# Sheet1.net
KiCad netlist of a schematic drawn in Altium Designer
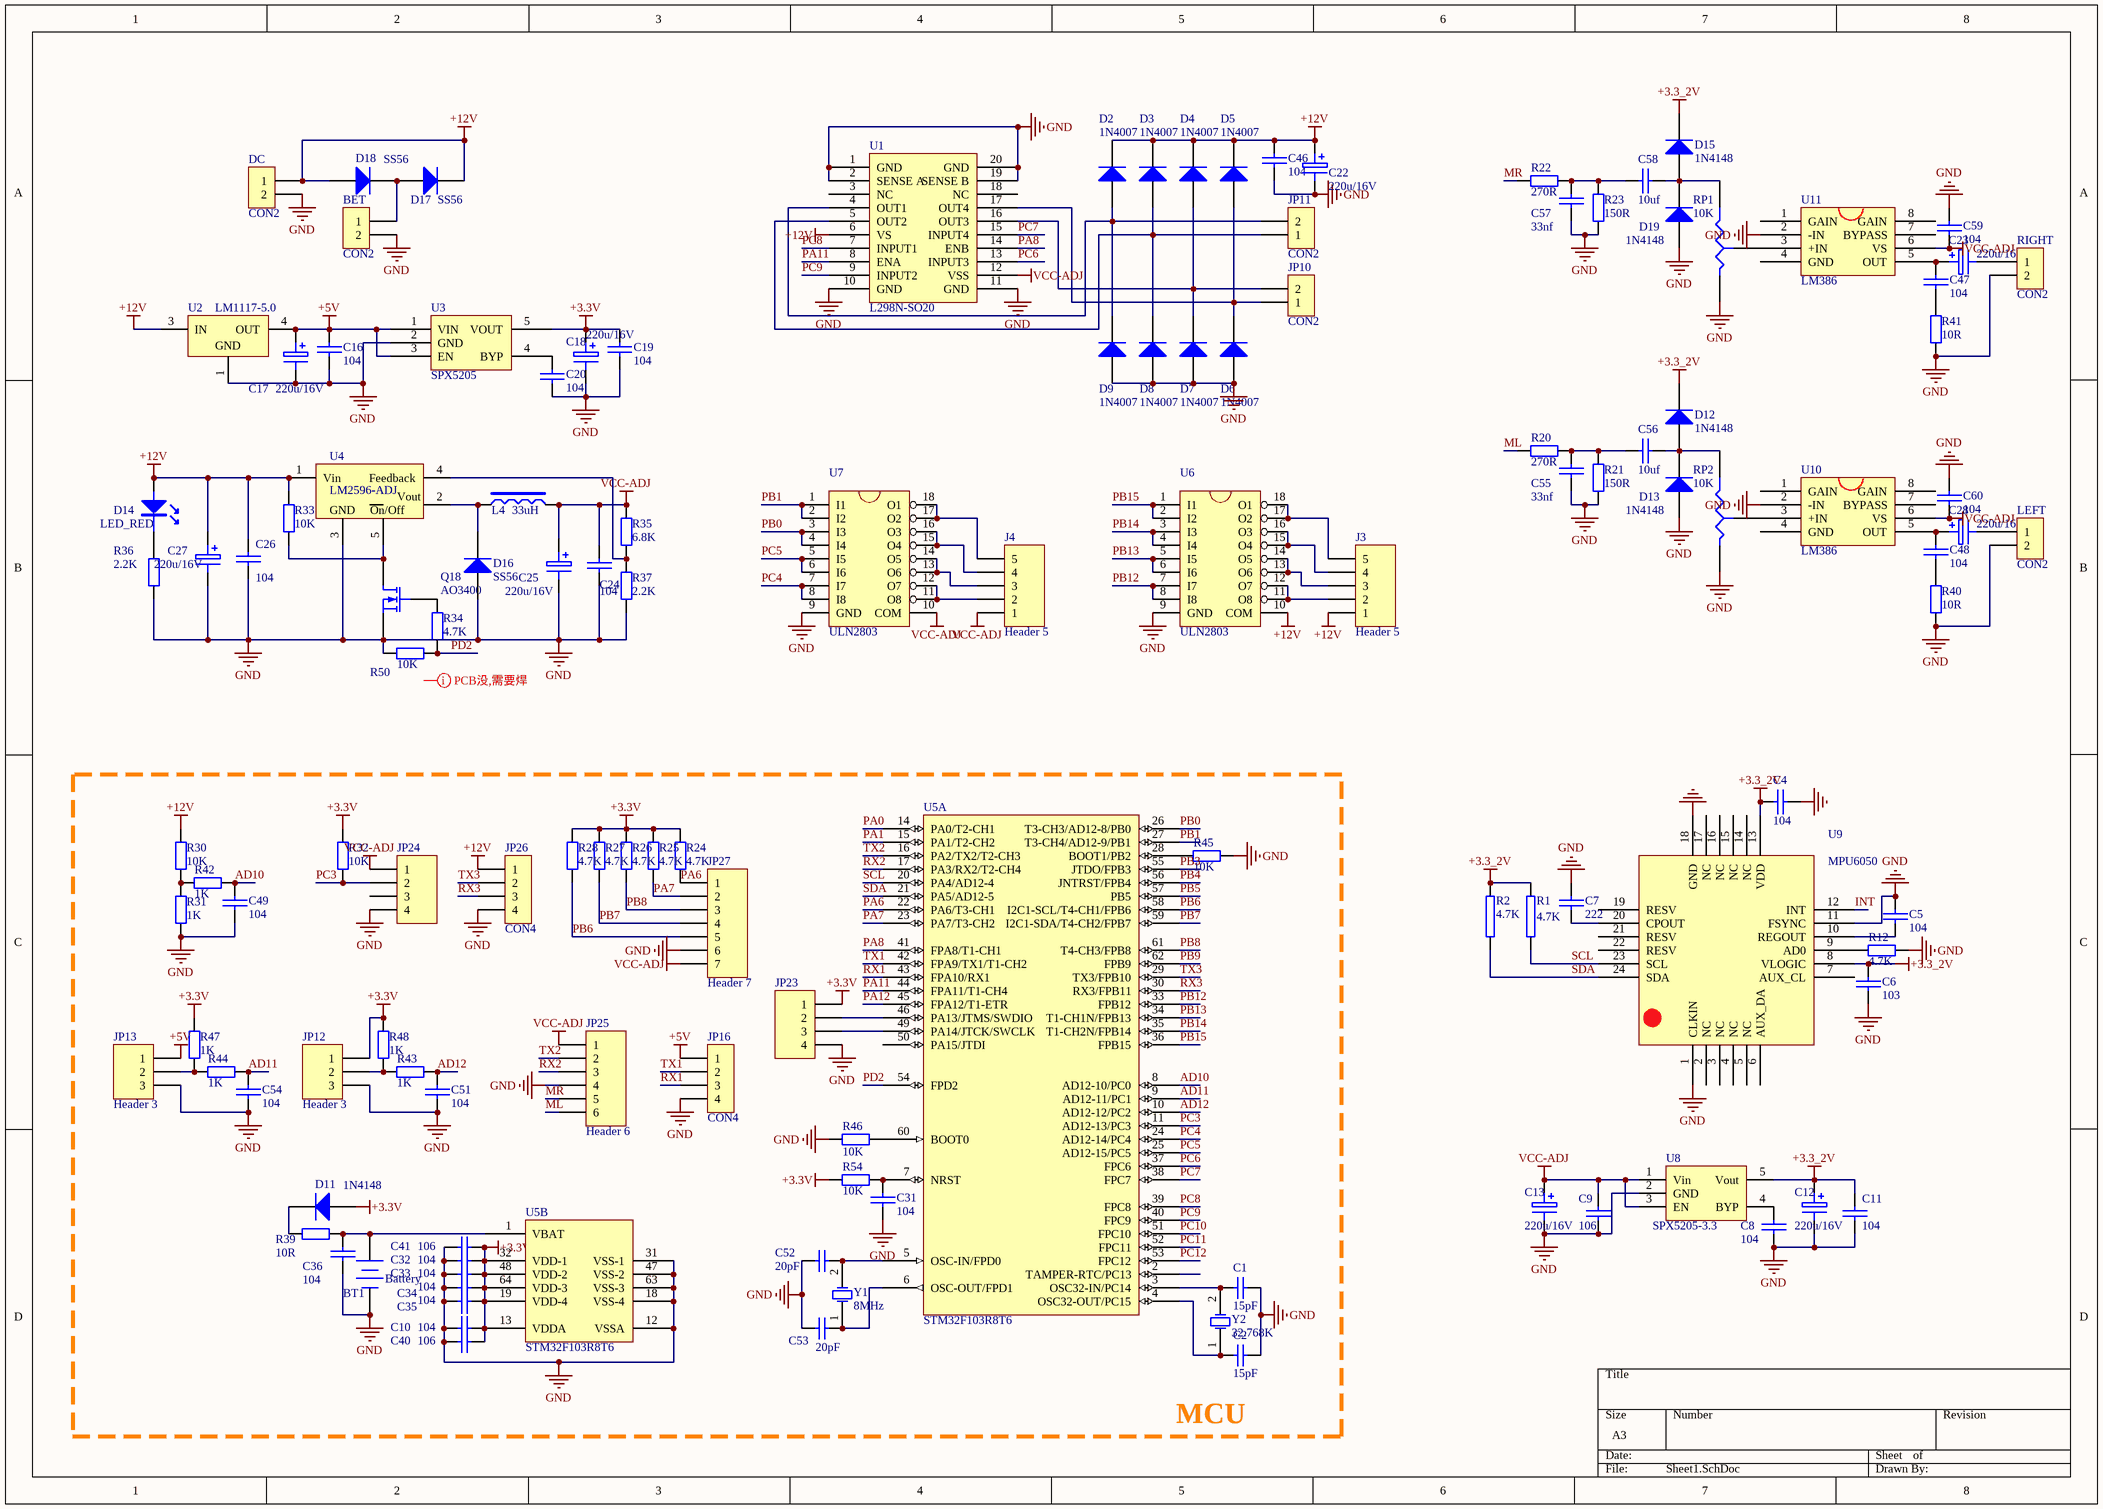
[diagram p0: Sheet1.SchDoc]

(export (version "E")
  (design (tool "Eeschema 10.0.6"))
  (components
    (comp (ref "BET")
      (value "CON2")
      (footprint "My Library:2PIN2.54")
      (description "Connector")
      (libsource (lib "*") (part "CON2"))
    )
    (comp (ref "BT1")
      (value "Battery")
      (footprint "BAT-2")
      (description "Multicell Battery")
      (fields (field (name "PUBLISHER") "Altium Limited"))
      (libsource (lib "Miscellaneous Devices") (part "Battery"))
    )
    (comp (ref "C1")
      (value "15pF")
      (footprint "0805")
      (description "Capacitor")
      (fields (field (name "PUBLISHER") "Altium Limited"))
      (libsource (lib "Miscellaneous Devices") (part "Cap"))
    )
    (comp (ref "C2")
      (value "15pF")
      (footprint "0805")
      (description "Capacitor")
      (fields (field (name "PUBLISHER") "Altium Limited"))
      (libsource (lib "Miscellaneous Devices") (part "Cap"))
    )
    (comp (ref "C4") (value "104") (footprint "0805") (libsource (lib "*") (part "CAP")))
    (comp (ref "C5") (value "104") (footprint "0805") (libsource (lib "*") (part "CAP_W")))
    (comp (ref "C6") (value "103") (footprint "0805") (libsource (lib "*") (part "CAP_W")))
    (comp (ref "C7") (value "222") (footprint "0805") (libsource (lib "*") (part "CAP_W")))
    (comp (ref "C8") (value "104") (footprint "0805") (libsource (lib "*") (part "CAP_W")))
    (comp (ref "C9") (value "106") (footprint "0805") (libsource (lib "*") (part "CAP_W")))
    (comp (ref "C10") (value "104") (footprint "0805") (libsource (lib "*") (part "CAP_W")))
    (comp (ref "C11") (value "104") (footprint "0805") (libsource (lib "*") (part "CAP_W")))
    (comp (ref "C12") (value "220u/16V") (footprint "C7542") (libsource (lib "*") (part "ELECTRO1_W")))
    (comp (ref "C13") (value "220u/16V") (footprint "C7542") (libsource (lib "*") (part "ELECTRO1_W")))
    (comp (ref "C16") (value "104") (footprint "0805") (libsource (lib "ddapwSch") (part "CAP_W")))
    (comp (ref "C17") (value "220u/16V") (footprint "C7542") (libsource (lib "*") (part "ELECTRO1_W")))
    (comp (ref "C18") (value "220u/16V") (footprint "C7542") (libsource (lib "*") (part "ELECTRO1_W")))
    (comp (ref "C19") (value "104") (footprint "0805") (libsource (lib "ddapwSch") (part "CAP_W")))
    (comp (ref "C20") (value "104") (footprint "0805") (libsource (lib "ddapwSch") (part "CAP_W")))
    (comp (ref "C22") (value "220u/16V") (footprint "C7542") (libsource (lib "*") (part "ELECTRO1_W")))
    (comp (ref "C23") (value "220u/16V") (footprint "C7542") (libsource (lib "*") (part "ELECTRO1_W")))
    (comp (ref "C24") (value "104") (footprint "0805") (libsource (lib "ddapwSch") (part "CAP_W")))
    (comp (ref "C25") (value "220u/16V") (footprint "C7542") (libsource (lib "*") (part "ELECTRO1_W")))
    (comp (ref "C26") (value "104") (footprint "0805") (libsource (lib "ddapwSch") (part "CAP_W")))
    (comp (ref "C27") (value "220u/16V") (footprint "C7542") (libsource (lib "*") (part "ELECTRO1_W")))
    (comp (ref "C28") (value "220u/16V") (footprint "C7542") (libsource (lib "*") (part "ELECTRO1_W")))
    (comp (ref "C31") (value "104") (footprint "0805") (libsource (lib "*") (part "CAP_W")))
    (comp (ref "C32") (value "104") (footprint "0805") (libsource (lib "*") (part "CAP_W")))
    (comp (ref "C33") (value "104") (footprint "0805") (libsource (lib "*") (part "CAP_W")))
    (comp (ref "C34") (value "104") (footprint "0805") (libsource (lib "*") (part "CAP_W")))
    (comp (ref "C35") (value "104") (footprint "0805") (libsource (lib "*") (part "CAP_W")))
    (comp (ref "C36") (value "104") (footprint "0805") (libsource (lib "*") (part "CAP_W")))
    (comp (ref "C40")
      (value "106")
      (footprint "0805")
      (description "Capacitor")
      (fields (field (name "PUBLISHER") "Altium Limited"))
      (libsource (lib "Miscellaneous Devices") (part "Cap"))
    )
    (comp (ref "C41")
      (value "106")
      (footprint "0805")
      (description "Capacitor")
      (fields (field (name "PUBLISHER") "Altium Limited"))
      (libsource (lib "Miscellaneous Devices") (part "Cap"))
    )
    (comp (ref "C46") (value "104") (footprint "0805") (libsource (lib "*") (part "CAP_W")))
    (comp (ref "C47") (value "104") (footprint "0805") (libsource (lib "*") (part "CAP_W")))
    (comp (ref "C48") (value "104") (footprint "0805") (libsource (lib "*") (part "CAP_W")))
    (comp (ref "C49") (value "104") (footprint "0805") (libsource (lib "*") (part "CAP_W")))
    (comp (ref "C51") (value "104") (footprint "0805") (libsource (lib "*") (part "CAP_W")))
    (comp (ref "C52")
      (value "20pF")
      (footprint "0805")
      (description "Capacitor")
      (fields (field (name "PUBLISHER") "Altium Limited"))
      (libsource (lib "Miscellaneous Devices") (part "Cap"))
    )
    (comp (ref "C53")
      (value "20pF")
      (footprint "My Library:0805")
      (description "Capacitor")
      (fields (field (name "PUBLISHER") "Altium Limited"))
      (libsource (lib "Miscellaneous Devices") (part "Cap"))
    )
    (comp (ref "C54") (value "104") (footprint "0805") (libsource (lib "*") (part "CAP_W")))
    (comp (ref "C55") (value "33nf") (footprint "0805") (libsource (lib "*") (part "CAP_W")))
    (comp (ref "C56") (value "10uf") (footprint "0805") (libsource (lib "") (part "CAP_W_1")))
    (comp (ref "C57") (value "33nf") (footprint "0805") (libsource (lib "*") (part "CAP_W")))
    (comp (ref "C58") (value "10uf") (footprint "0805") (libsource (lib "") (part "CAP_W_1")))
    (comp (ref "C59") (value "104") (footprint "0805") (libsource (lib "*") (part "CAP_W")))
    (comp (ref "C60") (value "104") (footprint "0805") (libsource (lib "*") (part "CAP_W")))
    (comp (ref "D2")
      (value "1N4007")
      (footprint "My Library:SMA")
      (description "Default Diode")
      (fields (field (name "PUBLISHER") "Altium Limited"))
      (libsource (lib "Miscellaneous Devices") (part "Diode"))
    )
    (comp (ref "D3")
      (value "1N4007")
      (footprint "My Library:SMA")
      (description "Default Diode")
      (fields (field (name "PUBLISHER") "Altium Limited"))
      (libsource (lib "Miscellaneous Devices") (part "Diode"))
    )
    (comp (ref "D4")
      (value "1N4007")
      (footprint "My Library:SMA")
      (description "Default Diode")
      (fields (field (name "PUBLISHER") "Altium Limited"))
      (libsource (lib "Miscellaneous Devices") (part "Diode"))
    )
    (comp (ref "D5")
      (value "1N4007")
      (footprint "My Library:SMA")
      (description "Default Diode")
      (fields (field (name "PUBLISHER") "Altium Limited"))
      (libsource (lib "Miscellaneous Devices") (part "Diode"))
    )
    (comp (ref "D6")
      (value "1N4007")
      (footprint "My Library:SMA")
      (description "Default Diode")
      (fields (field (name "PUBLISHER") "Altium Limited"))
      (libsource (lib "Miscellaneous Devices") (part "Diode"))
    )
    (comp (ref "D7")
      (value "1N4007")
      (footprint "My Library:SMA")
      (description "Default Diode")
      (fields (field (name "PUBLISHER") "Altium Limited"))
      (libsource (lib "Miscellaneous Devices") (part "Diode"))
    )
    (comp (ref "D8")
      (value "1N4007")
      (footprint "My Library:SMA")
      (description "Default Diode")
      (fields (field (name "PUBLISHER") "Altium Limited"))
      (libsource (lib "Miscellaneous Devices") (part "Diode"))
    )
    (comp (ref "D9")
      (value "1N4007")
      (footprint "My Library:SMA")
      (description "Default Diode")
      (fields (field (name "PUBLISHER") "Altium Limited"))
      (libsource (lib "Miscellaneous Devices") (part "Diode"))
    )
    (comp (ref "D11")
      (value "1N4148")
      (footprint "My Library:D1206")
      (description "Default Diode")
      (fields (field (name "PUBLISHER") "Altium Limited"))
      (libsource (lib "Miscellaneous Devices") (part "Diode"))
    )
    (comp (ref "D12")
      (value "1N4148")
      (footprint "My Library:D1206")
      (description "Default Diode")
      (fields (field (name "PUBLISHER") "Altium Limited"))
      (libsource (lib "Miscellaneous Devices") (part "Diode"))
    )
    (comp (ref "D13")
      (value "1N4148")
      (footprint "My Library:D1206")
      (description "Default Diode")
      (fields (field (name "PUBLISHER") "Altium Limited"))
      (libsource (lib "Miscellaneous Devices") (part "Diode"))
    )
    (comp (ref "D14")
      (value "LED_RED")
      (footprint "D0805")
      (libsource (lib "*") (part "Pro5E.tmp_UnNamed_101"))
    )
    (comp (ref "D15")
      (value "1N4148")
      (footprint "My Library:D1206")
      (description "Default Diode")
      (fields (field (name "PUBLISHER") "Altium Limited"))
      (libsource (lib "Miscellaneous Devices") (part "Diode"))
    )
    (comp (ref "D16")
      (value "SS56")
      (footprint "My Library:SMC")
      (description "Default Diode")
      (fields (field (name "PUBLISHER") "Altium Limited"))
      (libsource (lib "Miscellaneous Devices") (part "Diode"))
    )
    (comp (ref "D17")
      (value "SS56")
      (footprint "My Library:SMC")
      (description "Default Diode")
      (fields (field (name "PUBLISHER") "Altium Limited"))
      (libsource (lib "Miscellaneous Devices") (part "Diode"))
    )
    (comp (ref "D18")
      (value "SS56")
      (footprint "My Library:SMC")
      (description "Default Diode")
      (fields (field (name "PUBLISHER") "Altium Limited"))
      (libsource (lib "Miscellaneous Devices") (part "Diode"))
    )
    (comp (ref "D19")
      (value "1N4148")
      (footprint "My Library:D1206")
      (description "Default Diode")
      (fields (field (name "PUBLISHER") "Altium Limited"))
      (libsource (lib "Miscellaneous Devices") (part "Diode"))
    )
    (comp (ref "DC")
      (value "CON2")
      (footprint "My Library:2PIN2.54")
      (description "Connector")
      (libsource (lib "*") (part "CON2"))
    )
    (comp (ref "J3")
      (value "Header 5")
      (footprint "My Library:5PIN2.54")
      (description "Header, 5-Pin")
      (fields (field (name "PUBLISHER") "Altium Limited"))
      (libsource (lib "Miscellaneous Connectors") (part "Header 5"))
    )
    (comp (ref "J4")
      (value "Header 5")
      (footprint "My Library:5PIN2.54")
      (description "Header, 5-Pin")
      (fields (field (name "PUBLISHER") "Altium Limited"))
      (libsource (lib "Miscellaneous Connectors") (part "Header 5"))
    )
    (comp (ref "JP10")
      (value "CON2")
      (footprint "My Library:2PIN2.54")
      (description "Connector")
      (libsource (lib "") (part "CON2_1"))
    )
    (comp (ref "JP11")
      (value "CON2")
      (footprint "My Library:2PIN2.54")
      (description "Connector")
      (libsource (lib "") (part "CON2_1"))
    )
    (comp (ref "JP12")
      (value "Header 3")
      (footprint "My Library:3PIN2.54")
      (description "Header, 3-Pin")
      (fields (field (name "PUBLISHER") "Altium Limited"))
      (libsource (lib "Miscellaneous Connectors") (part "Header 3"))
    )
    (comp (ref "JP13")
      (value "Header 3")
      (footprint "My Library:3PIN2.54")
      (description "Header, 3-Pin")
      (fields (field (name "PUBLISHER") "Altium Limited"))
      (libsource (lib "Miscellaneous Connectors") (part "Header 3"))
    )
    (comp (ref "JP16")
      (value "CON4")
      (footprint "My Library:4PIN2.54")
      (description "Connector")
      (libsource (lib "Miscellaneous Devices") (part "CON4"))
    )
    (comp (ref "JP23")
      (value "Header 4")
      (footprint "My Library:4pin2.54-NEEDLE")
      (description "Header, 4-Pin")
      (fields (field (name "PUBLISHER") "Altium Limited"))
      (libsource (lib "Miscellaneous Connectors") (part "Header 4"))
    )
    (comp (ref "JP24")
      (value "Header 4")
      (footprint "My Library:4pin2.54-NEEDLE")
      (description "Header, 4-Pin")
      (fields (field (name "PUBLISHER") "Altium Limited"))
      (libsource (lib "") (part "Header 4_1"))
    )
    (comp (ref "JP25")
      (value "Header 6")
      (footprint "My Library:6PIN2.54")
      (description "Header, 6-Pin")
      (fields (field (name "PUBLISHER") "Altium Limited"))
      (libsource (lib "Miscellaneous Connectors") (part "Header 6"))
    )
    (comp (ref "JP26")
      (value "CON4")
      (footprint "My Library:4PIN2.54")
      (description "Connector")
      (libsource (lib "Miscellaneous Devices") (part "CON4"))
    )
    (comp (ref "JP27")
      (value "Header 7")
      (footprint "HDR1X7")
      (description "Header, 7-Pin")
      (fields (field (name "PUBLISHER") "Altium Limited"))
      (libsource (lib "Miscellaneous Connectors") (part "Header 7"))
    )
    (comp (ref "L4") (value "33uH") (footprint "SMD-12*12") (libsource (lib "*") (part "Pro4F.tmp_80uh_35")))
    (comp (ref "LEFT")
      (value "CON2")
      (footprint "My Library:2PIN2.54")
      (description "Connector")
      (libsource (lib "Miscellaneous Devices") (part "CON2"))
    )
    (comp (ref "Q18")
      (value "AO3400")
      (footprint "My Library:SOT-23-3")
      (description "N-Channel MOSFET")
      (fields (field (name "PUBLISHER") "Altium Limited"))
      (libsource (lib "Miscellaneous Devices") (part "MOSFET-N"))
    )
    (comp (ref "R1") (value "4.7K") (footprint "0805") (libsource (lib "*") (part "RES2")))
    (comp (ref "R2") (value "4.7K") (footprint "0805") (libsource (lib "*") (part "RES2")))
    (comp (ref "R12")
      (value "4.7K")
      (footprint "0805")
      (description "Resistor")
      (fields (field (name "PUBLISHER") "Altium Limited"))
      (libsource (lib "") (part "Res2_5"))
    )
    (comp (ref "R20")
      (value "270R")
      (footprint "My Library:0805")
      (description "Resistor")
      (fields (field (name "PUBLISHER") "Altium Limited"))
      (libsource (lib "") (part "Res2_1"))
    )
    (comp (ref "R21")
      (value "150R")
      (footprint "My Library:0805")
      (description "Resistor")
      (fields (field (name "PUBLISHER") "Altium Limited"))
      (libsource (lib "Miscellaneous Devices") (part "Res2"))
    )
    (comp (ref "R22")
      (value "270R")
      (footprint "My Library:0805")
      (description "Resistor")
      (fields (field (name "PUBLISHER") "Altium Limited"))
      (libsource (lib "") (part "Res2_7"))
    )
    (comp (ref "R23")
      (value "150R")
      (footprint "My Library:0805")
      (description "Resistor")
      (fields (field (name "PUBLISHER") "Altium Limited"))
      (libsource (lib "") (part "Res2_2"))
    )
    (comp (ref "R24")
      (value "4.7K")
      (footprint "My Library:0805")
      (description "Resistor")
      (fields (field (name "PUBLISHER") "Altium Limited"))
      (libsource (lib "") (part "Res2_2"))
    )
    (comp (ref "R25")
      (value "4.7K")
      (footprint "My Library:0805")
      (description "Resistor")
      (fields (field (name "PUBLISHER") "Altium Limited"))
      (libsource (lib "") (part "Res2_2"))
    )
    (comp (ref "R26")
      (value "4.7K")
      (footprint "My Library:0805")
      (description "Resistor")
      (fields (field (name "PUBLISHER") "Altium Limited"))
      (libsource (lib "") (part "Res2_2"))
    )
    (comp (ref "R27")
      (value "4.7K")
      (footprint "My Library:0805")
      (description "Resistor")
      (fields (field (name "PUBLISHER") "Altium Limited"))
      (libsource (lib "") (part "Res2_2"))
    )
    (comp (ref "R28")
      (value "4.7K")
      (footprint "My Library:0805")
      (description "Resistor")
      (fields (field (name "PUBLISHER") "Altium Limited"))
      (libsource (lib "") (part "Res2_2"))
    )
    (comp (ref "R30")
      (value "10K")
      (footprint "My Library:0805")
      (description "Resistor")
      (fields (field (name "PUBLISHER") "Altium Limited"))
      (libsource (lib "Miscellaneous Devices") (part "Res2"))
    )
    (comp (ref "R31")
      (value "1K")
      (footprint "My Library:0805")
      (description "Resistor")
      (fields (field (name "PUBLISHER") "Altium Limited"))
      (libsource (lib "Miscellaneous Devices") (part "Res2"))
    )
    (comp (ref "R32")
      (value "10K")
      (footprint "My Library:0805")
      (description "Resistor")
      (fields (field (name "PUBLISHER") "Altium Limited"))
      (libsource (lib "") (part "Res2_1"))
    )
    (comp (ref "R33")
      (value "10K")
      (footprint "0805")
      (description "Resistor")
      (fields (field (name "PUBLISHER") "Altium Limited"))
      (libsource (lib "") (part "Res2_3"))
    )
    (comp (ref "R34")
      (value "4.7K")
      (footprint "0805")
      (description "Resistor")
      (fields (field (name "PUBLISHER") "Altium Limited"))
      (libsource (lib "") (part "Res2_3"))
    )
    (comp (ref "R35")
      (value "6.8K")
      (footprint "0805")
      (description "Resistor")
      (fields (field (name "PUBLISHER") "Altium Limited"))
      (libsource (lib "") (part "Res2_6"))
    )
    (comp (ref "R36")
      (value "2.2K")
      (footprint "0805")
      (description "Resistor")
      (fields (field (name "PUBLISHER") "Altium Limited"))
      (libsource (lib "") (part "Res2_6"))
    )
    (comp (ref "R37")
      (value "2.2K")
      (footprint "0805")
      (description "Resistor")
      (fields (field (name "PUBLISHER") "Altium Limited"))
      (libsource (lib "") (part "Res2_6"))
    )
    (comp (ref "R39")
      (value "10R")
      (footprint "My Library:0805")
      (description "Resistor")
      (fields (field (name "PUBLISHER") "Altium Limited"))
      (libsource (lib "") (part "Res2_7"))
    )
    (comp (ref "R40")
      (value "10R")
      (footprint "My Library:0805")
      (description "Resistor")
      (fields (field (name "PUBLISHER") "Altium Limited"))
      (libsource (lib "") (part "Res2_2"))
    )
    (comp (ref "R41")
      (value "10R")
      (footprint "My Library:0805")
      (description "Resistor")
      (fields (field (name "PUBLISHER") "Altium Limited"))
      (libsource (lib "") (part "Res2_2"))
    )
    (comp (ref "R42")
      (value "1K")
      (footprint "My Library:0805")
      (description "Resistor")
      (fields (field (name "PUBLISHER") "Altium Limited"))
      (libsource (lib "") (part "Res2_1"))
    )
    (comp (ref "R43")
      (value "1K")
      (footprint "My Library:0805")
      (description "Resistor")
      (fields (field (name "PUBLISHER") "Altium Limited"))
      (libsource (lib "") (part "Res2_1"))
    )
    (comp (ref "R44")
      (value "1K")
      (footprint "My Library:0805")
      (description "Resistor")
      (fields (field (name "PUBLISHER") "Altium Limited"))
      (libsource (lib "") (part "Res2_1"))
    )
    (comp (ref "R45")
      (value "10K")
      (footprint "0805")
      (description "Resistor")
      (fields (field (name "PUBLISHER") "Altium Limited"))
      (libsource (lib "") (part "Res2_4"))
    )
    (comp (ref "R46")
      (value "10K")
      (footprint "0805")
      (description "Resistor")
      (fields (field (name "PUBLISHER") "Altium Limited"))
      (libsource (lib "") (part "Res2_4"))
    )
    (comp (ref "R47")
      (value "1K")
      (footprint "My Library:0805")
      (description "Resistor")
      (fields (field (name "PUBLISHER") "Altium Limited"))
      (libsource (lib "Miscellaneous Devices") (part "Res2"))
    )
    (comp (ref "R48")
      (value "1K")
      (footprint "My Library:0805")
      (description "Resistor")
      (fields (field (name "PUBLISHER") "Altium Limited"))
      (libsource (lib "Miscellaneous Devices") (part "Res2"))
    )
    (comp (ref "R50")
      (value "10K")
      (footprint "0805")
      (description "Resistor")
      (fields (field (name "PUBLISHER") "Altium Limited"))
      (libsource (lib "") (part "Res2_5"))
    )
    (comp (ref "R54")
      (value "10K")
      (footprint "My Library:0805")
      (description "Resistor")
      (fields (field (name "PUBLISHER") "Altium Limited"))
      (libsource (lib "Miscellaneous Devices") (part "Res2"))
    )
    (comp (ref "RIGHT")
      (value "CON2")
      (footprint "My Library:2PIN2.54")
      (description "Connector")
      (libsource (lib "Miscellaneous Devices") (part "CON2"))
    )
    (comp (ref "RP1")
      (value "10K")
      (footprint "My Library:RP")
      (description "Tapped Resistor")
      (fields (field (name "PUBLISHER") "Altium Limited"))
      (libsource (lib "Miscellaneous Devices") (part "Res Tap"))
    )
    (comp (ref "RP2")
      (value "10K")
      (footprint "My Library:RP")
      (description "Tapped Resistor")
      (fields (field (name "PUBLISHER") "Altium Limited"))
      (libsource (lib "Miscellaneous Devices") (part "Res Tap"))
    )
    (comp (ref "U1")
      (value "L298N-SO20")
      (footprint "PowerSO20")
      (libsource (lib "My Library") (part "L298N"))
    )
    (comp (ref "U2")
      (value "LM1117-5.0")
      (footprint "SOT-223")
      (description "800mA Low-Dropout Linear Regulator, 3-pin TO-252")
      (fields
        (field (name "PARTNUMBER") "LM1117IDT-3.3")
        (field (name "MANUFACTURER") "National Semiconductor")
        (field (name "PUBLISHER") "Altium Limited")
      )
      (libsource (lib "NSC LDO") (part "LM1117IDT-3.3"))
    )
    (comp (ref "U3")
      (value "SPX5205")
      (footprint "My Library:SOT-23-5")
      (description "VOLTAGE REGULATOR IC")
      (libsource (lib "DDD") (part "SPX5205"))
    )
    (comp (ref "U4") (value "LM2596-ADJ") (footprint "TO-263-5") (libsource (lib "*") (part "LM2575-5")))
    (comp (ref "U5")
      (value "STM32F103R8T6")
      (footprint "My Library:LTQFP64")
      (description "STM32 ARM-based 32-bit MCU with 64 Kbytes Flash, 64-pin LQFP, Industrial Temperature")
      (fields (field (name "PUBLISHER") "*"))
      (libsource (lib "STM32 SCH") (part "STM32F103R8T6"))
    )
    (comp (ref "U6")
      (value "ULN2803")
      (footprint "SOIC-18")
      (description "SOIC")
      (libsource (lib "IC集成芯片") (part "ULN2803"))
    )
    (comp (ref "U7")
      (value "ULN2803")
      (footprint "SOIC-18")
      (description "SOIC")
      (libsource (lib "IC集成芯片") (part "ULN2803"))
    )
    (comp (ref "U8")
      (value "SPX5205-3.3")
      (footprint "SOT-23-5")
      (libsource (lib "CMOSChip") (part "SPX5205"))
    )
    (comp (ref "U9")
      (value "MPU6050")
      (footprint "My Library:QFN4*4*0.9_24PIN")
      (libsource (lib "My Library") (part "MPU6050"))
    )
    (comp (ref "U10") (value "LM386") (footprint "SOP-8") (libsource (lib "My Library") (part "LM386")))
    (comp (ref "U11") (value "LM386") (footprint "SOP-8") (libsource (lib "My Library") (part "LM386")))
    (comp (ref "Y1")
      (value "8MHz")
      (footprint "My Library:SMD-5032")
      (description "Crystal Oscillator")
      (fields (field (name "PUBLISHER") "Altium Limited"))
      (libsource (lib "Miscellaneous Devices") (part "XTAL"))
    )
    (comp (ref "Y2")
      (value "32.768K")
      (footprint "My Library:SMD-5032")
      (description "Crystal Oscillator")
      (fields (field (name "PUBLISHER") "Altium Limited"))
      (libsource (lib "Miscellaneous Devices") (part "XTAL"))
    )
  )
  (nets
    (net (code "1") (name "+3.3V") (class "Default")
      (node (ref "C10") (pin "1") (pinfunction "1_1") (pintype "passive"))
      (node (ref "C18") (pin "1") (pinfunction "1_1") (pintype "passive"))
      (node (ref "C19") (pin "1") (pinfunction "1_1") (pintype "passive"))
      (node (ref "C32") (pin "2") (pinfunction "2_2") (pintype "passive"))
      (node (ref "C33") (pin "1") (pinfunction "1_1") (pintype "passive"))
      (node (ref "C34") (pin "2") (pinfunction "2_2") (pintype "passive"))
      (node (ref "C35") (pin "2") (pinfunction "2_2") (pintype "passive"))
      (node (ref "C40") (pin "2") (pinfunction "2_2") (pintype "passive"))
      (node (ref "C41") (pin "2") (pinfunction "2_2") (pintype "passive"))
      (node (ref "D11") (pin "1") (pinfunction "A_1") (pintype "passive"))
      (node (ref "JP12") (pin "1") (pinfunction "1_1") (pintype "passive"))
      (node (ref "JP23") (pin "1") (pinfunction "1_1") (pintype "passive"))
      (node (ref "R24") (pin "2") (pinfunction "2_2") (pintype "passive"))
      (node (ref "R25") (pin "2") (pinfunction "2_2") (pintype "passive"))
      (node (ref "R26") (pin "2") (pinfunction "2_2") (pintype "passive"))
      (node (ref "R27") (pin "2") (pinfunction "2_2") (pintype "passive"))
      (node (ref "R28") (pin "2") (pinfunction "2_2") (pintype "passive"))
      (node (ref "R32") (pin "1") (pinfunction "1_1") (pintype "passive"))
      (node (ref "R47") (pin "1") (pinfunction "1_1") (pintype "passive"))
      (node (ref "R48") (pin "1") (pinfunction "1_1") (pintype "passive"))
      (node (ref "R54") (pin "2") (pinfunction "2_2") (pintype "passive"))
      (node (ref "U3") (pin "5") (pinfunction "VOUT_5") (pintype "passive"))
      (node (ref "U5") (pin "13") (pinfunction "VDDA_13") (pintype "power_in"))
      (node (ref "U5") (pin "19") (pinfunction "VDD-4_19") (pintype "power_in"))
      (node (ref "U5") (pin "32") (pinfunction "VDD-1_32") (pintype "power_in"))
      (node (ref "U5") (pin "48") (pinfunction "VDD-2_48") (pintype "power_in"))
      (node (ref "U5") (pin "64") (pinfunction "VDD-3_64") (pintype "power_in"))
    )
    (net (code "2") (name "+3.3_2V") (class "Default")
      (node (ref "C11") (pin "2") (pinfunction "2_2") (pintype "passive"))
      (node (ref "C12") (pin "1") (pinfunction "1_1") (pintype "passive"))
      (node (ref "C4") (pin "1") (pintype "passive"))
      (node (ref "C6") (pin "1") (pinfunction "1_1") (pintype "passive"))
      (node (ref "D12") (pin "2") (pinfunction "K_2") (pintype "passive"))
      (node (ref "D15") (pin "2") (pinfunction "K_2") (pintype "passive"))
      (node (ref "R1") (pin "1") (pintype "passive"))
      (node (ref "R2") (pin "1") (pintype "passive"))
      (node (ref "U8") (pin "5") (pinfunction "Vout_5") (pintype "passive"))
      (node (ref "U9") (pin "13") (pinfunction "VDD_13") (pintype "passive"))
      (node (ref "U9") (pin "8") (pinfunction "VLOGIC_8") (pintype "passive"))
    )
    (net (code "3") (name "+5V") (class "Default")
      (node (ref "C16") (pin "1") (pinfunction "1_1") (pintype "passive"))
      (node (ref "C17") (pin "1") (pinfunction "1_1") (pintype "passive"))
      (node (ref "JP13") (pin "1") (pinfunction "1_1") (pintype "passive"))
      (node (ref "JP16") (pin "1") (pinfunction "1_1") (pintype "passive"))
      (node (ref "U2") (pin "4") (pinfunction "OUT_4") (pintype "power_in"))
      (node (ref "U3") (pin "1") (pinfunction "VIN_1") (pintype "passive"))
      (node (ref "U3") (pin "3") (pinfunction "EN_3") (pintype "passive"))
    )
    (net (code "4") (name "+12V") (class "Default")
      (node (ref "C22") (pin "1") (pinfunction "1_1") (pintype "passive"))
      (node (ref "C26") (pin "1") (pinfunction "1_1") (pintype "passive"))
      (node (ref "C27") (pin "1") (pinfunction "1_1") (pintype "passive"))
      (node (ref "C46") (pin "2") (pinfunction "2_2") (pintype "passive"))
      (node (ref "D14") (pin "A") (pintype "passive"))
      (node (ref "D17") (pin "2") (pinfunction "K_2") (pintype "passive"))
      (node (ref "D18") (pin "1") (pinfunction "A_1") (pintype "passive"))
      (node (ref "D2") (pin "2") (pinfunction "K_2") (pintype "passive"))
      (node (ref "D3") (pin "2") (pinfunction "K_2") (pintype "passive"))
      (node (ref "D4") (pin "2") (pinfunction "K_2") (pintype "passive"))
      (node (ref "D5") (pin "2") (pinfunction "K_2") (pintype "passive"))
      (node (ref "DC") (pin "1") (pinfunction "1_1") (pintype "passive"))
      (node (ref "J3") (pin "1") (pinfunction "1_1") (pintype "passive"))
      (node (ref "JP26") (pin "1") (pinfunction "1_1") (pintype "passive"))
      (node (ref "R30") (pin "1") (pinfunction "1_1") (pintype "passive"))
      (node (ref "R33") (pin "1") (pinfunction "1_1") (pintype "passive"))
      (node (ref "U1") (pin "6") (pinfunction "VS_6") (pintype "passive"))
      (node (ref "U2") (pin "3") (pinfunction "IN_3") (pintype "power_in"))
      (node (ref "U4") (pin "1") (pinfunction "Vin_1") (pintype "passive"))
      (node (ref "U6") (pin "10") (pinfunction "COM_10") (pintype "power_in"))
    )
    (net (code "5") (name "/AD10") (class "Default")
      (node (ref "C49") (pin "1") (pinfunction "1_1") (pintype "passive"))
      (node (ref "R42") (pin "1") (pinfunction "1_1") (pintype "passive"))
      (node (ref "U5") (pin "8") (pinfunction "AD12-10/PC0_8") (pintype "bidirectional"))
    )
    (net (code "6") (name "/AD11") (class "Default")
      (node (ref "C54") (pin "1") (pinfunction "1_1") (pintype "passive"))
      (node (ref "R44") (pin "1") (pinfunction "1_1") (pintype "passive"))
      (node (ref "U5") (pin "9") (pinfunction "AD12-11/PC1_9") (pintype "bidirectional"))
    )
    (net (code "7") (name "/AD12") (class "Default")
      (node (ref "C51") (pin "1") (pinfunction "1_1") (pintype "passive"))
      (node (ref "R43") (pin "1") (pinfunction "1_1") (pintype "passive"))
      (node (ref "U5") (pin "10") (pinfunction "AD12-12/PC2_10") (pintype "bidirectional"))
    )
    (net (code "8") (name "/INT") (class "Default")
      (node (ref "U9") (pin "12") (pinfunction "INT_12") (pintype "passive"))
    )
    (net (code "9") (name "/ML") (class "Default")
      (node (ref "JP25") (pin "6") (pinfunction "6_6") (pintype "passive"))
      (node (ref "R20") (pin "2") (pinfunction "2_2") (pintype "passive"))
    )
    (net (code "10") (name "/MR") (class "Default")
      (node (ref "JP25") (pin "5") (pinfunction "5_5") (pintype "passive"))
      (node (ref "R22") (pin "1") (pinfunction "1_1") (pintype "passive"))
    )
    (net (code "11") (name "/PA0") (class "Default")
      (node (ref "U5") (pin "14") (pinfunction "PA0/T2-CH1_14") (pintype "bidirectional"))
    )
    (net (code "12") (name "/PA1") (class "Default")
      (node (ref "U5") (pin "15") (pinfunction "PA1/T2-CH2_15") (pintype "bidirectional"))
    )
    (net (code "13") (name "/PA6") (class "Default")
      (node (ref "JP27") (pin "1") (pinfunction "1_1") (pintype "passive"))
      (node (ref "R24") (pin "1") (pinfunction "1_1") (pintype "passive"))
      (node (ref "U5") (pin "22") (pinfunction "PA6/T3-CH1_22") (pintype "bidirectional"))
    )
    (net (code "14") (name "/PA7") (class "Default")
      (node (ref "JP27") (pin "2") (pinfunction "2_2") (pintype "passive"))
      (node (ref "R25") (pin "1") (pinfunction "1_1") (pintype "passive"))
      (node (ref "U5") (pin "23") (pinfunction "PA7/T3-CH2_23") (pintype "bidirectional"))
    )
    (net (code "15") (name "/PA8") (class "Default")
      (node (ref "U1") (pin "14") (pinfunction "ENB_14") (pintype "passive"))
      (node (ref "U5") (pin "41") (pinfunction "FPA8/T1-CH1_41") (pintype "bidirectional"))
    )
    (net (code "16") (name "/PA11") (class "Default")
      (node (ref "U1") (pin "8") (pinfunction "ENA_8") (pintype "passive"))
      (node (ref "U5") (pin "44") (pinfunction "FPA11/T1-CH4_44") (pintype "bidirectional"))
    )
    (net (code "17") (name "/PA12") (class "Default")
      (node (ref "U5") (pin "45") (pinfunction "FPA12/T1-ETR_45") (pintype "bidirectional"))
    )
    (net (code "18") (name "/PB0") (class "Default")
      (node (ref "U5") (pin "26") (pinfunction "T3-CH3/AD12-8/PB0_26") (pintype "bidirectional"))
      (node (ref "U7") (pin "3") (pinfunction "I3_3") (pintype "passive"))
      (node (ref "U7") (pin "4") (pinfunction "I4_4") (pintype "passive"))
    )
    (net (code "19") (name "/PB1") (class "Default")
      (node (ref "U5") (pin "27") (pinfunction "T3-CH4/AD12-9/PB1_27") (pintype "bidirectional"))
      (node (ref "U7") (pin "1") (pinfunction "I1_1") (pintype "passive"))
      (node (ref "U7") (pin "2") (pinfunction "I2_2") (pintype "passive"))
    )
    (net (code "20") (name "/PB3") (class "Default")
      (node (ref "U5") (pin "55") (pinfunction "JTDO/FPB3_55") (pintype "bidirectional"))
    )
    (net (code "21") (name "/PB4") (class "Default")
      (node (ref "U5") (pin "56") (pinfunction "JNTRST/FPB4_56") (pintype "bidirectional"))
    )
    (net (code "22") (name "/PB5") (class "Default")
      (node (ref "U5") (pin "57") (pinfunction "PB5_57") (pintype "bidirectional"))
    )
    (net (code "23") (name "/PB6") (class "Default")
      (node (ref "JP27") (pin "5") (pinfunction "5_5") (pintype "passive"))
      (node (ref "R28") (pin "1") (pinfunction "1_1") (pintype "passive"))
      (node (ref "U5") (pin "58") (pinfunction "I2C1-SCL/T4-CH1/FPB6_58") (pintype "bidirectional"))
    )
    (net (code "24") (name "/PB7") (class "Default")
      (node (ref "JP27") (pin "4") (pinfunction "4_4") (pintype "passive"))
      (node (ref "R27") (pin "1") (pinfunction "1_1") (pintype "passive"))
      (node (ref "U5") (pin "59") (pinfunction "I2C1-SDA/T4-CH2/FPB7_59") (pintype "bidirectional"))
    )
    (net (code "25") (name "/PB8") (class "Default")
      (node (ref "JP27") (pin "3") (pinfunction "3_3") (pintype "passive"))
      (node (ref "R26") (pin "1") (pinfunction "1_1") (pintype "passive"))
      (node (ref "U5") (pin "61") (pinfunction "T4-CH3/FPB8_61") (pintype "bidirectional"))
    )
    (net (code "26") (name "/PB9") (class "Default")
      (node (ref "U5") (pin "62") (pinfunction "FPB9_62") (pintype "bidirectional"))
    )
    (net (code "27") (name "/PB12") (class "Default")
      (node (ref "U5") (pin "33") (pinfunction "FPB12_33") (pintype "bidirectional"))
      (node (ref "U6") (pin "7") (pinfunction "I7_7") (pintype "passive"))
      (node (ref "U6") (pin "8") (pinfunction "I8_8") (pintype "passive"))
    )
    (net (code "28") (name "/PB13") (class "Default")
      (node (ref "U5") (pin "34") (pinfunction "T1-CH1N/FPB13_34") (pintype "bidirectional"))
      (node (ref "U6") (pin "5") (pinfunction "I5_5") (pintype "passive"))
      (node (ref "U6") (pin "6") (pinfunction "I6_6") (pintype "passive"))
    )
    (net (code "29") (name "/PB14") (class "Default")
      (node (ref "U5") (pin "35") (pinfunction "T1-CH2N/FPB14_35") (pintype "bidirectional"))
      (node (ref "U6") (pin "3") (pinfunction "I3_3") (pintype "passive"))
      (node (ref "U6") (pin "4") (pinfunction "I4_4") (pintype "passive"))
    )
    (net (code "30") (name "/PB15") (class "Default")
      (node (ref "U5") (pin "36") (pinfunction "FPB15_36") (pintype "bidirectional"))
      (node (ref "U6") (pin "1") (pinfunction "I1_1") (pintype "passive"))
      (node (ref "U6") (pin "2") (pinfunction "I2_2") (pintype "passive"))
    )
    (net (code "31") (name "/PC3") (class "Default")
      (node (ref "JP24") (pin "2") (pinfunction "2_2") (pintype "passive"))
      (node (ref "R32") (pin "2") (pinfunction "2_2") (pintype "passive"))
      (node (ref "U5") (pin "11") (pinfunction "AD12-13/PC3_11") (pintype "bidirectional"))
    )
    (net (code "32") (name "/PC4") (class "Default")
      (node (ref "U5") (pin "24") (pinfunction "AD12-14/PC4_24") (pintype "bidirectional"))
      (node (ref "U7") (pin "7") (pinfunction "I7_7") (pintype "passive"))
      (node (ref "U7") (pin "8") (pinfunction "I8_8") (pintype "passive"))
    )
    (net (code "33") (name "/PC5") (class "Default")
      (node (ref "U5") (pin "25") (pinfunction "AD12-15/PC5_25") (pintype "bidirectional"))
      (node (ref "U7") (pin "5") (pinfunction "I5_5") (pintype "passive"))
      (node (ref "U7") (pin "6") (pinfunction "I6_6") (pintype "passive"))
    )
    (net (code "34") (name "/PC6") (class "Default")
      (node (ref "U1") (pin "13") (pinfunction "INPUT3_13") (pintype "passive"))
      (node (ref "U5") (pin "37") (pinfunction "FPC6_37") (pintype "bidirectional"))
    )
    (net (code "35") (name "/PC7") (class "Default")
      (node (ref "U1") (pin "15") (pinfunction "INPUT4_15") (pintype "passive"))
      (node (ref "U5") (pin "38") (pinfunction "FPC7_38") (pintype "bidirectional"))
    )
    (net (code "36") (name "/PC8") (class "Default")
      (node (ref "U1") (pin "7") (pinfunction "INPUT1_7") (pintype "passive"))
      (node (ref "U5") (pin "39") (pinfunction "FPC8_39") (pintype "bidirectional"))
    )
    (net (code "37") (name "/PC9") (class "Default")
      (node (ref "U1") (pin "9") (pinfunction "INPUT2_9") (pintype "passive"))
      (node (ref "U5") (pin "40") (pinfunction "FPC9_40") (pintype "bidirectional"))
    )
    (net (code "38") (name "/PC10") (class "Default")
      (node (ref "U5") (pin "51") (pinfunction "FPC10_51") (pintype "bidirectional"))
    )
    (net (code "39") (name "/PC11") (class "Default")
      (node (ref "U5") (pin "52") (pinfunction "FPC11_52") (pintype "bidirectional"))
    )
    (net (code "40") (name "/PC12") (class "Default")
      (node (ref "U5") (pin "53") (pinfunction "FPC12_53") (pintype "bidirectional"))
    )
    (net (code "41") (name "/PD2") (class "Default")
      (node (ref "R34") (pin "2") (pinfunction "2_2") (pintype "passive"))
      (node (ref "R50") (pin "1") (pinfunction "1_1") (pintype "passive"))
      (node (ref "U5") (pin "54") (pinfunction "FPD2_54") (pintype "bidirectional"))
    )
    (net (code "42") (name "/RX1") (class "Default")
      (node (ref "JP16") (pin "3") (pinfunction "3_3") (pintype "passive"))
      (node (ref "U5") (pin "43") (pinfunction "FPA10/RX1_43") (pintype "bidirectional"))
    )
    (net (code "43") (name "/RX2") (class "Default")
      (node (ref "JP25") (pin "3") (pinfunction "3_3") (pintype "passive"))
      (node (ref "U5") (pin "17") (pinfunction "PA3/RX2/T2-CH4_17") (pintype "bidirectional"))
    )
    (net (code "44") (name "/RX3") (class "Default")
      (node (ref "JP26") (pin "3") (pinfunction "3_3") (pintype "passive"))
      (node (ref "U5") (pin "30") (pinfunction "RX3/FPB11_30") (pintype "bidirectional"))
    )
    (net (code "45") (name "/SCL") (class "Default")
      (node (ref "R1") (pin "2") (pintype "passive"))
      (node (ref "U5") (pin "20") (pinfunction "PA4/AD12-4_20") (pintype "bidirectional"))
      (node (ref "U9") (pin "23") (pinfunction "SCL_23") (pintype "passive"))
    )
    (net (code "46") (name "/SDA") (class "Default")
      (node (ref "R2") (pin "2") (pintype "passive"))
      (node (ref "U5") (pin "21") (pinfunction "PA5/AD12-5_21") (pintype "bidirectional"))
      (node (ref "U9") (pin "24") (pinfunction "SDA_24") (pintype "passive"))
    )
    (net (code "47") (name "/TX1") (class "Default")
      (node (ref "JP16") (pin "2") (pinfunction "2_2") (pintype "passive"))
      (node (ref "U5") (pin "42") (pinfunction "FPA9/TX1/T1-CH2_42") (pintype "bidirectional"))
    )
    (net (code "48") (name "/TX2") (class "Default")
      (node (ref "JP25") (pin "2") (pinfunction "2_2") (pintype "passive"))
      (node (ref "U5") (pin "16") (pinfunction "PA2/TX2/T2-CH3_16") (pintype "bidirectional"))
    )
    (net (code "49") (name "/TX3") (class "Default")
      (node (ref "JP26") (pin "2") (pinfunction "2_2") (pintype "passive"))
      (node (ref "U5") (pin "29") (pinfunction "TX3/FPB10_29") (pintype "bidirectional"))
    )
    (net (code "50") (name "GND") (class "Default")
      (node (ref "BET") (pin "2") (pinfunction "2_2") (pintype "passive"))
      (node (ref "BT1") (pin "2") (pinfunction "-_2") (pintype "passive"))
      (node (ref "C1") (pin "2") (pinfunction "2_2") (pintype "passive"))
      (node (ref "C10") (pin "2") (pinfunction "2_2") (pintype "passive"))
      (node (ref "C11") (pin "1") (pinfunction "1_1") (pintype "passive"))
      (node (ref "C12") (pin "2") (pinfunction "2_2") (pintype "passive"))
      (node (ref "C13") (pin "2") (pinfunction "2_2") (pintype "passive"))
      (node (ref "C16") (pin "2") (pinfunction "2_2") (pintype "passive"))
      (node (ref "C17") (pin "2") (pinfunction "2_2") (pintype "passive"))
      (node (ref "C18") (pin "2") (pinfunction "2_2") (pintype "passive"))
      (node (ref "C19") (pin "2") (pinfunction "2_2") (pintype "passive"))
      (node (ref "C2") (pin "2") (pinfunction "2_2") (pintype "passive"))
      (node (ref "C20") (pin "2") (pinfunction "2_2") (pintype "passive"))
      (node (ref "C22") (pin "2") (pinfunction "2_2") (pintype "passive"))
      (node (ref "C24") (pin "2") (pinfunction "2_2") (pintype "passive"))
      (node (ref "C25") (pin "2") (pinfunction "2_2") (pintype "passive"))
      (node (ref "C26") (pin "2") (pinfunction "2_2") (pintype "passive"))
      (node (ref "C27") (pin "2") (pinfunction "2_2") (pintype "passive"))
      (node (ref "C31") (pin "1") (pinfunction "1_1") (pintype "passive"))
      (node (ref "C32") (pin "1") (pinfunction "1_1") (pintype "passive"))
      (node (ref "C33") (pin "2") (pinfunction "2_2") (pintype "passive"))
      (node (ref "C34") (pin "1") (pinfunction "1_1") (pintype "passive"))
      (node (ref "C35") (pin "1") (pinfunction "1_1") (pintype "passive"))
      (node (ref "C36") (pin "1") (pinfunction "1_1") (pintype "passive"))
      (node (ref "C4") (pin "2") (pintype "passive"))
      (node (ref "C40") (pin "1") (pinfunction "1_1") (pintype "passive"))
      (node (ref "C41") (pin "1") (pinfunction "1_1") (pintype "passive"))
      (node (ref "C46") (pin "1") (pinfunction "1_1") (pintype "passive"))
      (node (ref "C49") (pin "2") (pinfunction "2_2") (pintype "passive"))
      (node (ref "C5") (pin "1") (pinfunction "1_1") (pintype "passive"))
      (node (ref "C51") (pin "2") (pinfunction "2_2") (pintype "passive"))
      (node (ref "C52") (pin "2") (pinfunction "2_2") (pintype "passive"))
      (node (ref "C53") (pin "2") (pinfunction "2_2") (pintype "passive"))
      (node (ref "C54") (pin "2") (pinfunction "2_2") (pintype "passive"))
      (node (ref "C55") (pin "1") (pinfunction "1_1") (pintype "passive"))
      (node (ref "C57") (pin "1") (pinfunction "1_1") (pintype "passive"))
      (node (ref "C59") (pin "1") (pinfunction "1_1") (pintype "passive"))
      (node (ref "C6") (pin "2") (pinfunction "2_2") (pintype "passive"))
      (node (ref "C60") (pin "1") (pinfunction "1_1") (pintype "passive"))
      (node (ref "C7") (pin "1") (pinfunction "1_1") (pintype "passive"))
      (node (ref "C8") (pin "1") (pinfunction "1_1") (pintype "passive"))
      (node (ref "C9") (pin "1") (pinfunction "1_1") (pintype "passive"))
      (node (ref "D13") (pin "1") (pinfunction "A_1") (pintype "passive"))
      (node (ref "D16") (pin "1") (pinfunction "A_1") (pintype "passive"))
      (node (ref "D19") (pin "1") (pinfunction "A_1") (pintype "passive"))
      (node (ref "D6") (pin "1") (pinfunction "A_1") (pintype "passive"))
      (node (ref "D7") (pin "1") (pinfunction "A_1") (pintype "passive"))
      (node (ref "D8") (pin "1") (pinfunction "A_1") (pintype "passive"))
      (node (ref "D9") (pin "1") (pinfunction "A_1") (pintype "passive"))
      (node (ref "DC") (pin "2") (pinfunction "2_2") (pintype "passive"))
      (node (ref "JP12") (pin "3") (pinfunction "3_3") (pintype "passive"))
      (node (ref "JP13") (pin "3") (pinfunction "3_3") (pintype "passive"))
      (node (ref "JP16") (pin "4") (pinfunction "4_4") (pintype "passive"))
      (node (ref "JP23") (pin "4") (pinfunction "4_4") (pintype "passive"))
      (node (ref "JP24") (pin "4") (pinfunction "4_4") (pintype "passive"))
      (node (ref "JP25") (pin "4") (pinfunction "4_4") (pintype "passive"))
      (node (ref "JP26") (pin "4") (pinfunction "4_4") (pintype "passive"))
      (node (ref "JP27") (pin "6") (pinfunction "6_6") (pintype "passive"))
      (node (ref "LEFT") (pin "2") (pinfunction "2_2") (pintype "passive"))
      (node (ref "Q18") (pin "3") (pinfunction "S_3") (pintype "passive"))
      (node (ref "R12") (pin "1") (pinfunction "1_1") (pintype "passive"))
      (node (ref "R21") (pin "2") (pinfunction "2_2") (pintype "passive"))
      (node (ref "R23") (pin "1") (pinfunction "1_1") (pintype "passive"))
      (node (ref "R31") (pin "2") (pinfunction "2_2") (pintype "passive"))
      (node (ref "R36") (pin "1") (pinfunction "1_1") (pintype "passive"))
      (node (ref "R37") (pin "1") (pinfunction "1_1") (pintype "passive"))
      (node (ref "R40") (pin "1") (pinfunction "1_1") (pintype "passive"))
      (node (ref "R41") (pin "1") (pinfunction "1_1") (pintype "passive"))
      (node (ref "R45") (pin "2") (pinfunction "2_2") (pintype "passive"))
      (node (ref "R46") (pin "1") (pinfunction "1_1") (pintype "passive"))
      (node (ref "R50") (pin "2") (pinfunction "2_2") (pintype "passive"))
      (node (ref "RIGHT") (pin "2") (pinfunction "2_2") (pintype "passive"))
      (node (ref "RP1") (pin "1") (pinfunction "A_1") (pintype "passive"))
      (node (ref "RP2") (pin "1") (pinfunction "A_1") (pintype "passive"))
      (node (ref "U1") (pin "1") (pinfunction "GND_1") (pintype "passive"))
      (node (ref "U1") (pin "10") (pinfunction "GND_10") (pintype "passive"))
      (node (ref "U1") (pin "11") (pinfunction "GND_11") (pintype "passive"))
      (node (ref "U1") (pin "19") (pinfunction "SENSE_B_19") (pintype "passive"))
      (node (ref "U1") (pin "2") (pinfunction "SENSE_A_2") (pintype "passive"))
      (node (ref "U1") (pin "20") (pinfunction "GND_20") (pintype "passive"))
      (node (ref "U10") (pin "2") (pinfunction "-IN_2") (pintype "passive"))
      (node (ref "U11") (pin "2") (pinfunction "-IN_2") (pintype "passive"))
      (node (ref "U2") (pin "1") (pinfunction "GND_1") (pintype "power_in"))
      (node (ref "U3") (pin "2") (pinfunction "GND_2") (pintype "passive"))
      (node (ref "U4") (pin "3") (pintype "passive"))
      (node (ref "U5") (pin "12") (pinfunction "VSSA_12") (pintype "power_in"))
      (node (ref "U5") (pin "18") (pinfunction "VSS-4_18") (pintype "power_in"))
      (node (ref "U5") (pin "31") (pinfunction "VSS-1_31") (pintype "power_in"))
      (node (ref "U5") (pin "47") (pinfunction "VSS-2_47") (pintype "power_in"))
      (node (ref "U5") (pin "63") (pinfunction "VSS-3_63") (pintype "power_in"))
      (node (ref "U6") (pin "9") (pinfunction "GND_9") (pintype "passive"))
      (node (ref "U7") (pin "9") (pinfunction "GND_9") (pintype "passive"))
      (node (ref "U8") (pin "2") (pinfunction "GND_2") (pintype "passive"))
      (node (ref "U9") (pin "1") (pinfunction "CLKIN_1") (pintype "passive"))
      (node (ref "U9") (pin "11") (pinfunction "FSYNC_11") (pintype "passive"))
      (node (ref "U9") (pin "18") (pinfunction "GND_18") (pintype "passive"))
    )
    (net (code "51") (name "Net-(BT1-+)") (class "Default")
      (node (ref "BT1") (pin "1") (pinfunction "+_1") (pintype "passive"))
      (node (ref "C36") (pin "2") (pinfunction "2_2") (pintype "passive"))
      (node (ref "R39") (pin "2") (pinfunction "2_2") (pintype "passive"))
      (node (ref "U5") (pin "1") (pinfunction "VBAT_1") (pintype "power_in"))
    )
    (net (code "52") (name "Net-(C23-Pad2)") (class "Default")
      (node (ref "C23") (pin "2") (pinfunction "2_2") (pintype "passive"))
      (node (ref "RIGHT") (pin "1") (pinfunction "1_1") (pintype "passive"))
    )
    (net (code "53") (name "Net-(C28-Pad2)") (class "Default")
      (node (ref "C28") (pin "2") (pinfunction "2_2") (pintype "passive"))
      (node (ref "LEFT") (pin "1") (pinfunction "1_1") (pintype "passive"))
    )
    (net (code "54") (name "Net-(C47-Pad1)") (class "Default")
      (node (ref "C47") (pin "1") (pinfunction "1_1") (pintype "passive"))
      (node (ref "R41") (pin "2") (pinfunction "2_2") (pintype "passive"))
    )
    (net (code "55") (name "Net-(C48-Pad1)") (class "Default")
      (node (ref "C48") (pin "1") (pinfunction "1_1") (pintype "passive"))
      (node (ref "R40") (pin "2") (pinfunction "2_2") (pintype "passive"))
    )
    (net (code "56") (name "Net-(C55-Pad2)") (class "Default")
      (node (ref "C55") (pin "2") (pinfunction "2_2") (pintype "passive"))
      (node (ref "C56") (pin "2") (pinfunction "2_2") (pintype "passive"))
      (node (ref "R20") (pin "1") (pinfunction "1_1") (pintype "passive"))
      (node (ref "R21") (pin "1") (pinfunction "1_1") (pintype "passive"))
    )
    (net (code "57") (name "Net-(C57-Pad2)") (class "Default")
      (node (ref "C57") (pin "2") (pinfunction "2_2") (pintype "passive"))
      (node (ref "C58") (pin "2") (pinfunction "2_2") (pintype "passive"))
      (node (ref "R22") (pin "2") (pinfunction "2_2") (pintype "passive"))
      (node (ref "R23") (pin "2") (pinfunction "2_2") (pintype "passive"))
    )
    (net (code "58") (name "Net-(D2-A)") (class "Default")
      (node (ref "D2") (pin "1") (pinfunction "A_1") (pintype "passive"))
      (node (ref "D9") (pin "2") (pinfunction "K_2") (pintype "passive"))
      (node (ref "JP11") (pin "2") (pinfunction "2_2") (pintype "passive"))
      (node (ref "U1") (pin "4") (pinfunction "OUT1_4") (pintype "passive"))
    )
    (net (code "59") (name "Net-(D3-A)") (class "Default")
      (node (ref "D3") (pin "1") (pinfunction "A_1") (pintype "passive"))
      (node (ref "D8") (pin "2") (pinfunction "K_2") (pintype "passive"))
      (node (ref "JP11") (pin "1") (pinfunction "1_1") (pintype "passive"))
      (node (ref "U1") (pin "5") (pinfunction "OUT2_5") (pintype "passive"))
    )
    (net (code "60") (name "Net-(D4-A)") (class "Default")
      (node (ref "D4") (pin "1") (pinfunction "A_1") (pintype "passive"))
      (node (ref "D7") (pin "2") (pinfunction "K_2") (pintype "passive"))
      (node (ref "JP10") (pin "2") (pinfunction "2_2") (pintype "passive"))
      (node (ref "U1") (pin "16") (pinfunction "OUT3_16") (pintype "passive"))
    )
    (net (code "61") (name "Net-(D5-A)") (class "Default")
      (node (ref "D5") (pin "1") (pinfunction "A_1") (pintype "passive"))
      (node (ref "D6") (pin "2") (pinfunction "K_2") (pintype "passive"))
      (node (ref "JP10") (pin "1") (pinfunction "1_1") (pintype "passive"))
      (node (ref "U1") (pin "17") (pinfunction "OUT4_17") (pintype "passive"))
    )
    (net (code "62") (name "Net-(D11-K)") (class "Default")
      (node (ref "D11") (pin "2") (pinfunction "K_2") (pintype "passive"))
      (node (ref "R39") (pin "1") (pinfunction "1_1") (pintype "passive"))
    )
    (net (code "63") (name "Net-(D12-A)") (class "Default")
      (node (ref "C56") (pin "1") (pinfunction "1_1") (pintype "passive"))
      (node (ref "D12") (pin "1") (pinfunction "A_1") (pintype "passive"))
      (node (ref "D13") (pin "2") (pinfunction "K_2") (pintype "passive"))
      (node (ref "RP2") (pin "2") (pinfunction "B_2") (pintype "passive"))
    )
    (net (code "64") (name "Net-(D14-PadK)") (class "Default")
      (node (ref "D14") (pin "K") (pintype "passive"))
      (node (ref "R36") (pin "2") (pinfunction "2_2") (pintype "passive"))
    )
    (net (code "65") (name "Net-(D15-A)") (class "Default")
      (node (ref "C58") (pin "1") (pinfunction "1_1") (pintype "passive"))
      (node (ref "D15") (pin "1") (pinfunction "A_1") (pintype "passive"))
      (node (ref "D19") (pin "2") (pinfunction "K_2") (pintype "passive"))
      (node (ref "RP1") (pin "2") (pinfunction "B_2") (pintype "passive"))
    )
    (net (code "66") (name "Net-(D16-K)") (class "Default")
      (node (ref "D16") (pin "2") (pinfunction "K_2") (pintype "passive"))
      (node (ref "L4") (pin "1") (pintype "passive"))
      (node (ref "U4") (pin "2") (pintype "passive"))
    )
    (net (code "67") (name "Net-(D17-A)") (class "Default")
      (node (ref "BET") (pin "1") (pinfunction "1_1") (pintype "passive"))
      (node (ref "D17") (pin "1") (pinfunction "A_1") (pintype "passive"))
      (node (ref "D18") (pin "2") (pinfunction "K_2") (pintype "passive"))
    )
    (net (code "68") (name "Net-(JP12-Pad2)") (class "Default")
      (node (ref "JP12") (pin "2") (pinfunction "2_2") (pintype "passive"))
      (node (ref "R43") (pin "2") (pinfunction "2_2") (pintype "passive"))
      (node (ref "R48") (pin "2") (pinfunction "2_2") (pintype "passive"))
    )
    (net (code "69") (name "Net-(JP13-Pad2)") (class "Default")
      (node (ref "JP13") (pin "2") (pinfunction "2_2") (pintype "passive"))
      (node (ref "R44") (pin "2") (pinfunction "2_2") (pintype "passive"))
      (node (ref "R47") (pin "2") (pinfunction "2_2") (pintype "passive"))
    )
    (net (code "70") (name "Net-(Q18-D)") (class "Default")
      (node (ref "Q18") (pin "1") (pinfunction "D_1") (pintype "passive"))
      (node (ref "R33") (pin "2") (pinfunction "2_2") (pintype "passive"))
      (node (ref "U4") (pin "5") (pintype "passive"))
    )
    (net (code "71") (name "Net-(Q18-G)") (class "Default")
      (node (ref "Q18") (pin "2") (pinfunction "G_2") (pintype "passive"))
      (node (ref "R34") (pin "1") (pinfunction "1_1") (pintype "passive"))
    )
    (net (code "72") (name "Net-(R30-Pad2)") (class "Default")
      (node (ref "R30") (pin "2") (pinfunction "2_2") (pintype "passive"))
      (node (ref "R31") (pin "1") (pinfunction "1_1") (pintype "passive"))
      (node (ref "R42") (pin "2") (pinfunction "2_2") (pintype "passive"))
    )
    (net (code "73") (name "Net-(RP1-TAP)") (class "Default")
      (node (ref "RP1") (pin "3") (pinfunction "TAP_3") (pintype "passive"))
      (node (ref "U11") (pin "3") (pinfunction "+IN_3") (pintype "passive"))
    )
    (net (code "74") (name "Net-(RP2-TAP)") (class "Default")
      (node (ref "RP2") (pin "3") (pinfunction "TAP_3") (pintype "passive"))
      (node (ref "U10") (pin "3") (pinfunction "+IN_3") (pintype "passive"))
    )
    (net (code "75") (name "Net-(U3-BYP)") (class "Default")
      (node (ref "C20") (pin "1") (pinfunction "1_1") (pintype "passive"))
      (node (ref "U3") (pin "4") (pinfunction "BYP_4") (pintype "passive"))
    )
    (net (code "76") (name "Net-(U4-Feedback)") (class "Default")
      (node (ref "R35") (pin "1") (pinfunction "1_1") (pintype "passive"))
      (node (ref "R37") (pin "2") (pinfunction "2_2") (pintype "passive"))
      (node (ref "U4") (pin "4") (pinfunction "Feedback_4") (pintype "passive"))
    )
    (net (code "77") (name "Net-(U5A-BOOT0)") (class "Default")
      (node (ref "R46") (pin "2") (pinfunction "2_2") (pintype "passive"))
      (node (ref "U5") (pin "60") (pinfunction "BOOT0_60") (pintype "input"))
    )
    (net (code "78") (name "Net-(U5A-BOOT1{slash}PB2)") (class "Default")
      (node (ref "R45") (pin "1") (pinfunction "1_1") (pintype "passive"))
      (node (ref "U5") (pin "28") (pinfunction "BOOT1/PB2_28") (pintype "bidirectional"))
    )
    (net (code "79") (name "Net-(U5A-NRST)") (class "Default")
      (node (ref "C31") (pin "2") (pinfunction "2_2") (pintype "passive"))
      (node (ref "R54") (pin "1") (pinfunction "1_1") (pintype "passive"))
      (node (ref "U5") (pin "7") (pinfunction "NRST_7") (pintype "bidirectional"))
    )
    (net (code "80") (name "Net-(U5A-OSC-IN{slash}FPD0)") (class "Default")
      (node (ref "C52") (pin "1") (pinfunction "1_1") (pintype "passive"))
      (node (ref "U5") (pin "5") (pinfunction "OSC-IN/FPD0_5") (pintype "input"))
      (node (ref "Y1") (pin "2") (pinfunction "OSC2_2") (pintype "passive"))
    )
    (net (code "81") (name "Net-(U5A-OSC-OUT{slash}FPD1)") (class "Default")
      (node (ref "C53") (pin "1") (pinfunction "1_1") (pintype "passive"))
      (node (ref "U5") (pin "6") (pinfunction "OSC-OUT/FPD1_6") (pintype "output"))
      (node (ref "Y1") (pin "1") (pinfunction "OSC1_1") (pintype "passive"))
    )
    (net (code "82") (name "Net-(U5A-OSC32-IN{slash}PC14)") (class "Default")
      (node (ref "C1") (pin "1") (pinfunction "1_1") (pintype "passive"))
      (node (ref "U5") (pin "3") (pinfunction "OSC32-IN/PC14_3") (pintype "bidirectional"))
      (node (ref "Y2") (pin "2") (pinfunction "OSC2_2") (pintype "passive"))
    )
    (net (code "83") (name "Net-(U5A-OSC32-OUT{slash}PC15)") (class "Default")
      (node (ref "C2") (pin "1") (pinfunction "1_1") (pintype "passive"))
      (node (ref "U5") (pin "4") (pinfunction "OSC32-OUT/PC15_4") (pintype "bidirectional"))
      (node (ref "Y2") (pin "1") (pinfunction "OSC1_1") (pintype "passive"))
    )
    (net (code "84") (name "Net-(U5A-PA13{slash}JTMS{slash}SWDIO)") (class "Default")
      (node (ref "JP23") (pin "2") (pinfunction "2_2") (pintype "passive"))
      (node (ref "U5") (pin "46") (pinfunction "PA13/JTMS/SWDIO_46") (pintype "bidirectional"))
    )
    (net (code "85") (name "Net-(U5A-PA14{slash}JTCK{slash}SWCLK)") (class "Default")
      (node (ref "JP23") (pin "3") (pinfunction "3_3") (pintype "passive"))
      (node (ref "U5") (pin "49") (pinfunction "PA14/JTCK/SWCLK_49") (pintype "bidirectional"))
    )
    (net (code "86") (name "Net-(U6-O1)") (class "Default")
      (node (ref "J3") (pin "5") (pinfunction "5_5") (pintype "passive"))
      (node (ref "U6") (pin "17") (pinfunction "O2_17") (pintype "passive"))
      (node (ref "U6") (pin "18") (pinfunction "O1_18") (pintype "passive"))
    )
    (net (code "87") (name "Net-(U6-O3)") (class "Default")
      (node (ref "J3") (pin "4") (pinfunction "4_4") (pintype "passive"))
      (node (ref "U6") (pin "15") (pinfunction "O4_15") (pintype "passive"))
      (node (ref "U6") (pin "16") (pinfunction "O3_16") (pintype "passive"))
    )
    (net (code "88") (name "Net-(U6-O5)") (class "Default")
      (node (ref "J3") (pin "3") (pinfunction "3_3") (pintype "passive"))
      (node (ref "U6") (pin "13") (pinfunction "O6_13") (pintype "passive"))
      (node (ref "U6") (pin "14") (pinfunction "O5_14") (pintype "passive"))
    )
    (net (code "89") (name "Net-(U6-O7)") (class "Default")
      (node (ref "J3") (pin "2") (pinfunction "2_2") (pintype "passive"))
      (node (ref "U6") (pin "11") (pinfunction "O8_11") (pintype "passive"))
      (node (ref "U6") (pin "12") (pinfunction "O7_12") (pintype "passive"))
    )
    (net (code "90") (name "Net-(U7-O1)") (class "Default")
      (node (ref "J4") (pin "5") (pinfunction "5_5") (pintype "passive"))
      (node (ref "U7") (pin "17") (pinfunction "O2_17") (pintype "passive"))
      (node (ref "U7") (pin "18") (pinfunction "O1_18") (pintype "passive"))
    )
    (net (code "91") (name "Net-(U7-O3)") (class "Default")
      (node (ref "J4") (pin "4") (pinfunction "4_4") (pintype "passive"))
      (node (ref "U7") (pin "15") (pinfunction "O4_15") (pintype "passive"))
      (node (ref "U7") (pin "16") (pinfunction "O3_16") (pintype "passive"))
    )
    (net (code "92") (name "Net-(U7-O5)") (class "Default")
      (node (ref "J4") (pin "3") (pinfunction "3_3") (pintype "passive"))
      (node (ref "U7") (pin "13") (pinfunction "O6_13") (pintype "passive"))
      (node (ref "U7") (pin "14") (pinfunction "O5_14") (pintype "passive"))
    )
    (net (code "93") (name "Net-(U7-O7)") (class "Default")
      (node (ref "J4") (pin "2") (pinfunction "2_2") (pintype "passive"))
      (node (ref "U7") (pin "11") (pinfunction "O8_11") (pintype "passive"))
      (node (ref "U7") (pin "12") (pinfunction "O7_12") (pintype "passive"))
    )
    (net (code "94") (name "Net-(U8-BYP)") (class "Default")
      (node (ref "C8") (pin "2") (pinfunction "2_2") (pintype "passive"))
      (node (ref "U8") (pin "4") (pinfunction "BYP_4") (pintype "passive"))
    )
    (net (code "95") (name "Net-(U9-AD0)") (class "Default")
      (node (ref "R12") (pin "2") (pinfunction "2_2") (pintype "passive"))
      (node (ref "U9") (pin "9") (pinfunction "AD0_9") (pintype "passive"))
    )
    (net (code "96") (name "Net-(U9-CPOUT)") (class "Default")
      (node (ref "C7") (pin "2") (pinfunction "2_2") (pintype "passive"))
      (node (ref "U9") (pin "20") (pinfunction "CPOUT_20") (pintype "passive"))
    )
    (net (code "97") (name "Net-(U9-REGOUT)") (class "Default")
      (node (ref "C5") (pin "2") (pinfunction "2_2") (pintype "passive"))
      (node (ref "U9") (pin "10") (pinfunction "REGOUT_10") (pintype "passive"))
    )
    (net (code "98") (name "Net-(U10-OUT)") (class "Default")
      (node (ref "C28") (pin "1") (pinfunction "1_1") (pintype "passive"))
      (node (ref "C48") (pin "2") (pinfunction "2_2") (pintype "passive"))
      (node (ref "U10") (pin "5") (pinfunction "OUT_5") (pintype "passive"))
    )
    (net (code "99") (name "Net-(U11-OUT)") (class "Default")
      (node (ref "C23") (pin "1") (pinfunction "1_1") (pintype "passive"))
      (node (ref "C47") (pin "2") (pinfunction "2_2") (pintype "passive"))
      (node (ref "U11") (pin "5") (pinfunction "OUT_5") (pintype "passive"))
    )
    (net (code "100") (name "VCC-ADJ") (class "Default")
      (node (ref "C13") (pin "1") (pinfunction "1_1") (pintype "passive"))
      (node (ref "C24") (pin "1") (pinfunction "1_1") (pintype "passive"))
      (node (ref "C25") (pin "1") (pinfunction "1_1") (pintype "passive"))
      (node (ref "C59") (pin "2") (pinfunction "2_2") (pintype "passive"))
      (node (ref "C60") (pin "2") (pinfunction "2_2") (pintype "passive"))
      (node (ref "C9") (pin "2") (pinfunction "2_2") (pintype "passive"))
      (node (ref "J4") (pin "1") (pinfunction "1_1") (pintype "passive"))
      (node (ref "JP24") (pin "1") (pinfunction "1_1") (pintype "passive"))
      (node (ref "JP25") (pin "1") (pinfunction "1_1") (pintype "passive"))
      (node (ref "JP27") (pin "7") (pinfunction "7_7") (pintype "passive"))
      (node (ref "L4") (pin "2") (pintype "passive"))
      (node (ref "R35") (pin "2") (pinfunction "2_2") (pintype "passive"))
      (node (ref "U1") (pin "12") (pinfunction "VSS_12") (pintype "passive"))
      (node (ref "U10") (pin "6") (pinfunction "VS_6") (pintype "passive"))
      (node (ref "U11") (pin "6") (pinfunction "VS_6") (pintype "passive"))
      (node (ref "U7") (pin "10") (pinfunction "COM_10") (pintype "power_in"))
      (node (ref "U8") (pin "1") (pinfunction "Vin_1") (pintype "passive"))
      (node (ref "U8") (pin "3") (pinfunction "EN_3") (pintype "passive"))
    )
    (net (code "101") (name "unconnected-(JP24-Pad3)") (class "Default")
      (node (ref "JP24") (pin "3") (pinfunction "3_3") (pintype "passive"))
    )
    (net (code "102") (name "unconnected-(U1-NC-Pad3)") (class "Default")
      (node (ref "U1") (pin "3") (pinfunction "NC_3") (pintype "passive"))
    )
    (net (code "103") (name "unconnected-(U1-NC-Pad18)") (class "Default")
      (node (ref "U1") (pin "18") (pinfunction "NC_18") (pintype "passive"))
    )
    (net (code "104") (name "unconnected-(U5A-PA15{slash}JTDI-Pad50)") (class "Default")
      (node (ref "U5") (pin "50") (pinfunction "PA15/JTDI_50") (pintype "bidirectional"))
    )
    (net (code "105") (name "unconnected-(U5A-TAMPER-RTC{slash}PC13-Pad2)") (class "Default")
      (node (ref "U5") (pin "2") (pinfunction "TAMPER-RTC/PC13_2") (pintype "bidirectional"))
    )
    (net (code "106") (name "unconnected-(U9-AUX_CL-Pad7)") (class "Default")
      (node (ref "U9") (pin "7") (pinfunction "AUX_CL_7") (pintype "passive"))
    )
    (net (code "107") (name "unconnected-(U9-AUX_DA-Pad6)") (class "Default")
      (node (ref "U9") (pin "6") (pinfunction "AUX_DA_6") (pintype "passive"))
    )
    (net (code "108") (name "unconnected-(U9-NC-Pad2)") (class "Default")
      (node (ref "U9") (pin "2") (pinfunction "NC_2") (pintype "passive"))
    )
    (net (code "109") (name "unconnected-(U9-NC-Pad3)") (class "Default")
      (node (ref "U9") (pin "3") (pinfunction "NC_3") (pintype "passive"))
    )
    (net (code "110") (name "unconnected-(U9-NC-Pad4)") (class "Default")
      (node (ref "U9") (pin "4") (pinfunction "NC_4") (pintype "passive"))
    )
    (net (code "111") (name "unconnected-(U9-NC-Pad5)") (class "Default")
      (node (ref "U9") (pin "5") (pinfunction "NC_5") (pintype "passive"))
    )
    (net (code "112") (name "unconnected-(U9-NC-Pad14)") (class "Default")
      (node (ref "U9") (pin "14") (pinfunction "NC_14") (pintype "passive"))
    )
    (net (code "113") (name "unconnected-(U9-NC-Pad15)") (class "Default")
      (node (ref "U9") (pin "15") (pinfunction "NC_15") (pintype "passive"))
    )
    (net (code "114") (name "unconnected-(U9-NC-Pad16)") (class "Default")
      (node (ref "U9") (pin "16") (pinfunction "NC_16") (pintype "passive"))
    )
    (net (code "115") (name "unconnected-(U9-NC-Pad17)") (class "Default")
      (node (ref "U9") (pin "17") (pinfunction "NC_17") (pintype "passive"))
    )
    (net (code "116") (name "unconnected-(U9-RESV-Pad19)") (class "Default")
      (node (ref "U9") (pin "19") (pinfunction "RESV_19") (pintype "passive"))
    )
    (net (code "117") (name "unconnected-(U9-RESV-Pad21)") (class "Default")
      (node (ref "U9") (pin "21") (pinfunction "RESV_21") (pintype "passive"))
    )
    (net (code "118") (name "unconnected-(U9-RESV-Pad22)") (class "Default")
      (node (ref "U9") (pin "22") (pinfunction "RESV_22") (pintype "passive"))
    )
    (net (code "119") (name "unconnected-(U10-BYPASS-Pad7)") (class "Default")
      (node (ref "U10") (pin "7") (pinfunction "BYPASS_7") (pintype "passive"))
    )
    (net (code "120") (name "unconnected-(U10-GAIN-Pad1)") (class "Default")
      (node (ref "U10") (pin "1") (pinfunction "GAIN_1") (pintype "passive"))
    )
    (net (code "121") (name "unconnected-(U10-GAIN-Pad8)") (class "Default")
      (node (ref "U10") (pin "8") (pinfunction "GAIN_8") (pintype "passive"))
    )
    (net (code "122") (name "unconnected-(U10-GND-Pad4)") (class "Default")
      (node (ref "U10") (pin "4") (pinfunction "GND_4") (pintype "passive"))
    )
    (net (code "123") (name "unconnected-(U11-BYPASS-Pad7)") (class "Default")
      (node (ref "U11") (pin "7") (pinfunction "BYPASS_7") (pintype "passive"))
    )
    (net (code "124") (name "unconnected-(U11-GAIN-Pad1)") (class "Default")
      (node (ref "U11") (pin "1") (pinfunction "GAIN_1") (pintype "passive"))
    )
    (net (code "125") (name "unconnected-(U11-GAIN-Pad8)") (class "Default")
      (node (ref "U11") (pin "8") (pinfunction "GAIN_8") (pintype "passive"))
    )
    (net (code "126") (name "unconnected-(U11-GND-Pad4)") (class "Default")
      (node (ref "U11") (pin "4") (pinfunction "GND_4") (pintype "passive"))
    )
  )
)
